# power.net
KiCad netlist of a schematic drawn in Altium Designer
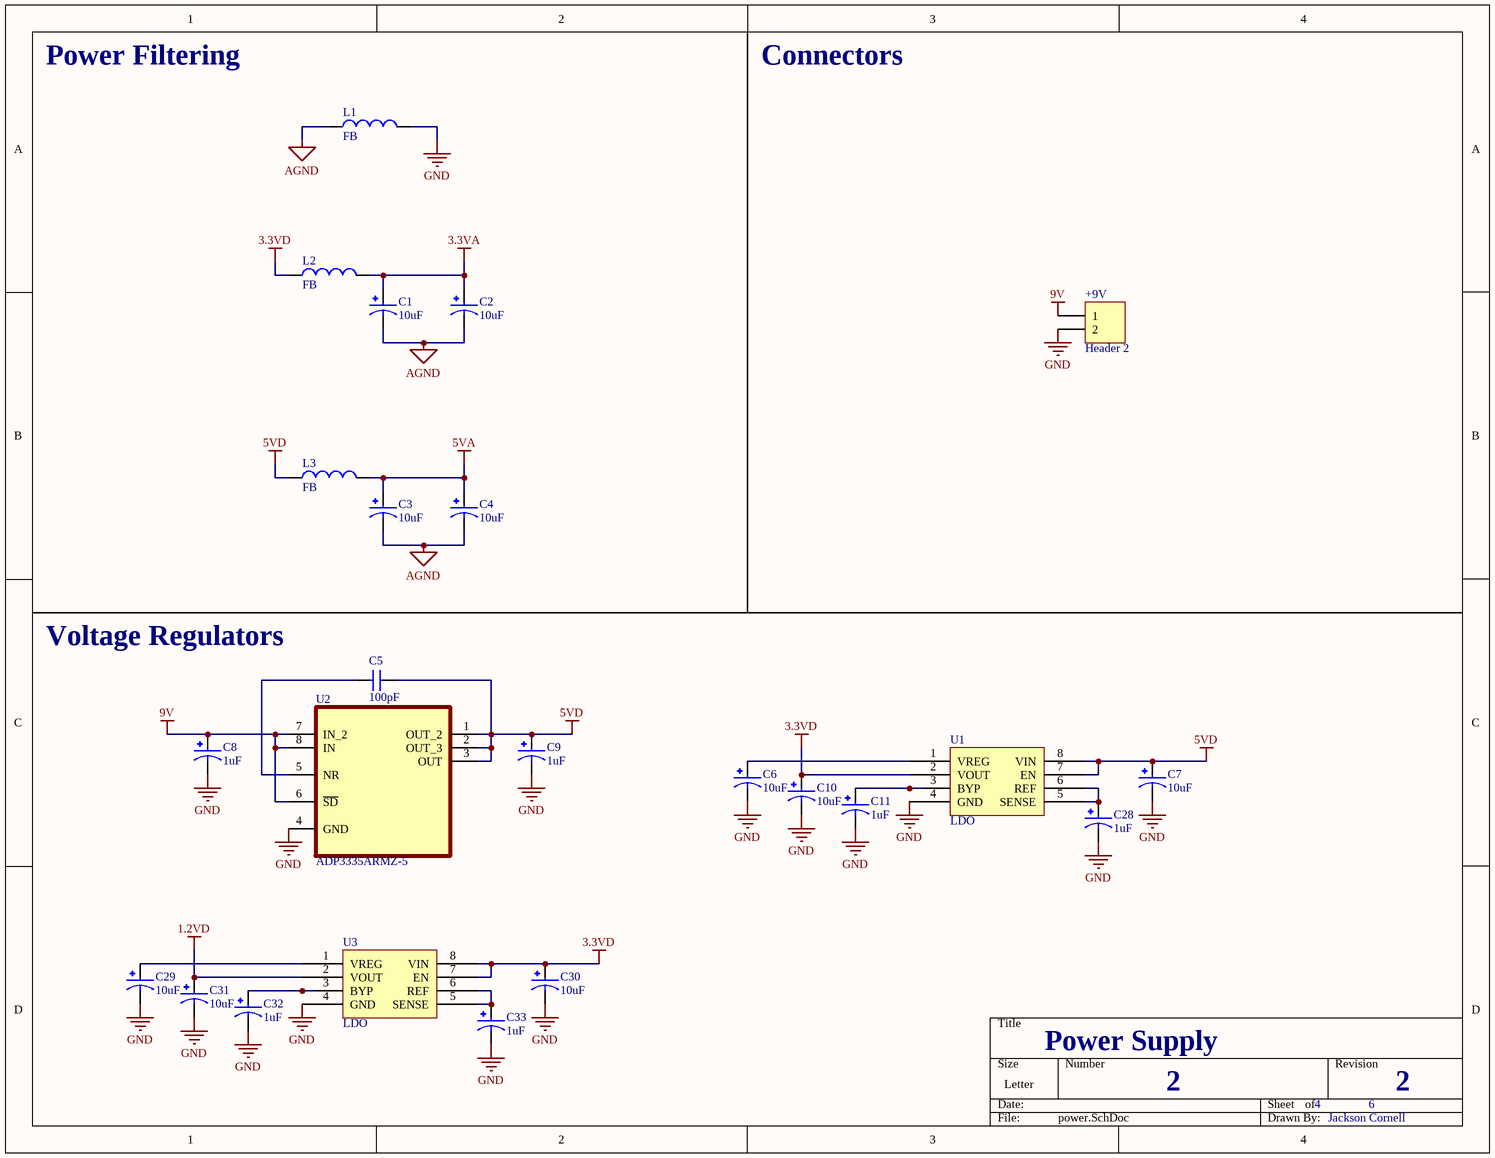
[diagram p0: power.SchDoc]

(export (version "E")
  (design (tool "Eeschema 10.0.6"))
  (components
    (comp (ref "+9V")
      (value "Header 2")
      (footprint "HDR1X2")
      (description "Header, 2-Pin")
      (fields (field (name "PUBLISHER") "Altium Limited"))
      (libsource (lib "Miscellaneous Connectors") (part "Header 2"))
    )
    (comp (ref "C1")
      (value "10uF")
      (footprint "CAPPRD200W50D500H1250")
      (description "Aluminum Electrolytic Capacitors, 220uF, 6.3V, -40 to 105C")
      (fields (field (name "MF") "Panasonic") (field (name "MP") "EEUFS0J221B"))
      (libsource (lib "EEUFS0J221B") (part "EEUFS0J221B"))
    )
    (comp (ref "C2")
      (value "10uF")
      (footprint "CAPPRD200W50D500H1250")
      (description "Aluminum Electrolytic Capacitors, 220uF, 6.3V, -40 to 105C")
      (fields (field (name "MF") "Panasonic") (field (name "MP") "EEUFS0J221B"))
      (libsource (lib "EEUFS0J221B") (part "EEUFS0J221B"))
    )
    (comp (ref "C3")
      (value "10uF")
      (footprint "CAPPRD200W50D500H1250")
      (description "Aluminum Electrolytic Capacitors, 220uF, 6.3V, -40 to 105C")
      (fields (field (name "MF") "Panasonic") (field (name "MP") "EEUFS0J221B"))
      (libsource (lib "EEUFS0J221B") (part "EEUFS0J221B"))
    )
    (comp (ref "C4")
      (value "10uF")
      (footprint "CAPPRD200W50D500H1250")
      (description "Aluminum Electrolytic Capacitors, 220uF, 6.3V, -40 to 105C")
      (fields (field (name "MF") "Panasonic") (field (name "MP") "EEUFS0J221B"))
      (libsource (lib "EEUFS0J221B") (part "EEUFS0J221B"))
    )
    (comp (ref "C5")
      (value "100pF")
      (footprint "CAPC0805")
      (fields (field (name "Comment") "Cap"))
      (libsource (lib "Passives") (part "Cap"))
    )
    (comp (ref "C6")
      (value "10uF")
      (footprint "CAPPRD200W50D500H1250")
      (description "Aluminum Electrolytic Capacitors, 220uF, 6.3V, -40 to 105C")
      (fields (field (name "MF") "Panasonic") (field (name "MP") "EEUFS0J221B"))
      (libsource (lib "EEUFS0J221B") (part "EEUFS0J221B"))
    )
    (comp (ref "C7")
      (value "10uF")
      (footprint "CAPPRD200W50D500H1250")
      (description "Aluminum Electrolytic Capacitors, 220uF, 6.3V, -40 to 105C")
      (fields (field (name "MF") "Panasonic") (field (name "MP") "EEUFS0J221B"))
      (libsource (lib "EEUFS0J221B") (part "EEUFS0J221B"))
    )
    (comp (ref "C8")
      (value "1uF")
      (footprint "CAPPRD200W50D500H1250")
      (description "Aluminum Electrolytic Capacitors, 220uF, 6.3V, -40 to 105C")
      (fields (field (name "MF") "Panasonic") (field (name "MP") "EEUFS0J221B"))
      (libsource (lib "EEUFS0J221B") (part "EEUFS0J221B"))
    )
    (comp (ref "C9")
      (value "1uF")
      (footprint "CAPPRD200W50D500H1250")
      (description "Aluminum Electrolytic Capacitors, 220uF, 6.3V, -40 to 105C")
      (fields (field (name "MF") "Panasonic") (field (name "MP") "EEUFS0J221B"))
      (libsource (lib "EEUFS0J221B") (part "EEUFS0J221B"))
    )
    (comp (ref "C10")
      (value "10uF")
      (footprint "CAPPRD200W50D500H1250")
      (description "Aluminum Electrolytic Capacitors, 220uF, 6.3V, -40 to 105C")
      (fields (field (name "MF") "Panasonic") (field (name "MP") "EEUFS0J221B"))
      (libsource (lib "EEUFS0J221B") (part "EEUFS0J221B"))
    )
    (comp (ref "C11")
      (value "1uF")
      (footprint "CAPPRD200W50D500H1250")
      (description "Aluminum Electrolytic Capacitors, 220uF, 6.3V, -40 to 105C")
      (fields (field (name "MF") "Panasonic") (field (name "MP") "EEUFS0J221B"))
      (libsource (lib "EEUFS0J221B") (part "EEUFS0J221B"))
    )
    (comp (ref "C28")
      (value "1uF")
      (footprint "CAPPRD200W50D500H1250")
      (description "Aluminum Electrolytic Capacitors, 220uF, 6.3V, -40 to 105C")
      (fields (field (name "MF") "Panasonic") (field (name "MP") "EEUFS0J221B"))
      (libsource (lib "EEUFS0J221B") (part "EEUFS0J221B"))
    )
    (comp (ref "C29")
      (value "10uF")
      (footprint "CAPPRD200W50D500H1250")
      (description "Aluminum Electrolytic Capacitors, 220uF, 6.3V, -40 to 105C")
      (fields (field (name "MF") "Panasonic") (field (name "MP") "EEUFS0J221B"))
      (libsource (lib "EEUFS0J221B") (part "EEUFS0J221B"))
    )
    (comp (ref "C30")
      (value "10uF")
      (footprint "CAPPRD200W50D500H1250")
      (description "Aluminum Electrolytic Capacitors, 220uF, 6.3V, -40 to 105C")
      (fields (field (name "MF") "Panasonic") (field (name "MP") "EEUFS0J221B"))
      (libsource (lib "EEUFS0J221B") (part "EEUFS0J221B"))
    )
    (comp (ref "C31")
      (value "10uF")
      (footprint "CAPPRD200W50D500H1250")
      (description "Aluminum Electrolytic Capacitors, 220uF, 6.3V, -40 to 105C")
      (fields (field (name "MF") "Panasonic") (field (name "MP") "EEUFS0J221B"))
      (libsource (lib "EEUFS0J221B") (part "EEUFS0J221B"))
    )
    (comp (ref "C32")
      (value "1uF")
      (footprint "CAPPRD200W50D500H1250")
      (description "Aluminum Electrolytic Capacitors, 220uF, 6.3V, -40 to 105C")
      (fields (field (name "MF") "Panasonic") (field (name "MP") "EEUFS0J221B"))
      (libsource (lib "EEUFS0J221B") (part "EEUFS0J221B"))
    )
    (comp (ref "C33")
      (value "1uF")
      (footprint "CAPPRD200W50D500H1250")
      (description "Aluminum Electrolytic Capacitors, 220uF, 6.3V, -40 to 105C")
      (fields (field (name "MF") "Panasonic") (field (name "MP") "EEUFS0J221B"))
      (libsource (lib "EEUFS0J221B") (part "EEUFS0J221B"))
    )
    (comp (ref "L1")
      (value "FB")
      (footprint "RES0805")
      (description "Inductor")
      (fields (field (name "PUBLISHER") "Altium Limited"))
      (libsource (lib "Miscellaneous Devices") (part "Inductor"))
    )
    (comp (ref "L2")
      (value "FB")
      (footprint "RES0805")
      (description "Inductor")
      (fields (field (name "PUBLISHER") "Altium Limited"))
      (libsource (lib "Miscellaneous Devices") (part "Inductor"))
    )
    (comp (ref "L3")
      (value "FB")
      (footprint "RES0805")
      (description "Inductor")
      (fields (field (name "PUBLISHER") "Altium Limited"))
      (libsource (lib "Miscellaneous Devices") (part "Inductor"))
    )
    (comp (ref "U1")
      (value "LDO")
      (footprint "SOIC127P600X175-9N")
      (libsource (lib "ADM7154") (part "ADM7154"))
    )
    (comp (ref "U2")
      (value "ADP3335ARMZ-5")
      (footprint "SOP65P490X110-8N")
      (description "Linear Voltage Regulator IC 1 Output 500mA 8-MSOP")
      (fields (field (name "MP") "ADP3335ARMZ-3.3") (field (name "MF") "Analog Devices"))
      (libsource (lib "ADP3335ARMZ-3.3") (part "ADP3335ARMZ-3.3"))
    )
    (comp (ref "U3")
      (value "LDO")
      (footprint "SOIC127P600X175-9N")
      (libsource (lib "ADM7154") (part "ADM7154"))
    )
  )
  (nets
    (net (code "1") (name "1.2VD") (class "Default")
      (node (ref "C31") (pin "P") (pinfunction "P_P") (pintype "passive"))
      (node (ref "U3") (pin "2") (pinfunction "VOUT_2") (pintype "passive"))
    )
    (net (code "2") (name "3.3VA") (class "Default")
      (node (ref "C1") (pin "P") (pinfunction "P_P") (pintype "passive"))
      (node (ref "C2") (pin "P") (pinfunction "P_P") (pintype "passive"))
      (node (ref "L2") (pin "2") (pinfunction "2_2") (pintype "passive"))
    )
    (net (code "3") (name "3.3VD") (class "Default")
      (node (ref "C10") (pin "P") (pinfunction "P_P") (pintype "passive"))
      (node (ref "C30") (pin "P") (pinfunction "P_P") (pintype "passive"))
      (node (ref "L2") (pin "1") (pinfunction "1_1") (pintype "passive"))
      (node (ref "U1") (pin "2") (pinfunction "VOUT_2") (pintype "passive"))
      (node (ref "U3") (pin "7") (pinfunction "EN_7") (pintype "passive"))
      (node (ref "U3") (pin "8") (pinfunction "VIN_8") (pintype "passive"))
    )
    (net (code "4") (name "5VA") (class "Default")
      (node (ref "C3") (pin "P") (pinfunction "P_P") (pintype "passive"))
      (node (ref "C4") (pin "P") (pinfunction "P_P") (pintype "passive"))
      (node (ref "L3") (pin "2") (pinfunction "2_2") (pintype "passive"))
    )
    (net (code "5") (name "5VD") (class "Default")
      (node (ref "C5") (pin "2") (pinfunction "B_2") (pintype "passive"))
      (node (ref "C7") (pin "P") (pinfunction "P_P") (pintype "passive"))
      (node (ref "C9") (pin "P") (pinfunction "P_P") (pintype "passive"))
      (node (ref "L3") (pin "1") (pinfunction "1_1") (pintype "passive"))
      (node (ref "U1") (pin "7") (pinfunction "EN_7") (pintype "passive"))
      (node (ref "U1") (pin "8") (pinfunction "VIN_8") (pintype "passive"))
      (node (ref "U2") (pin "1") (pinfunction "OUT_2_1") (pintype "passive"))
      (node (ref "U2") (pin "2") (pinfunction "OUT_3_2") (pintype "passive"))
      (node (ref "U2") (pin "3") (pinfunction "OUT_3") (pintype "passive"))
    )
    (net (code "6") (name "9V") (class "Default")
      (node (ref "+9V") (pin "1") (pinfunction "1_1") (pintype "passive"))
      (node (ref "C8") (pin "P") (pinfunction "P_P") (pintype "passive"))
      (node (ref "U2") (pin "6") (pinfunction "~{SD}_6") (pintype "passive"))
      (node (ref "U2") (pin "7") (pinfunction "IN_2_7") (pintype "passive"))
      (node (ref "U2") (pin "8") (pinfunction "IN_8") (pintype "passive"))
    )
    (net (code "7") (name "AGND") (class "Default")
      (node (ref "C1") (pin "N") (pinfunction "N_N") (pintype "passive"))
      (node (ref "C2") (pin "N") (pinfunction "N_N") (pintype "passive"))
      (node (ref "C3") (pin "N") (pinfunction "N_N") (pintype "passive"))
      (node (ref "C4") (pin "N") (pinfunction "N_N") (pintype "passive"))
      (node (ref "L1") (pin "1") (pinfunction "1_1") (pintype "passive"))
    )
    (net (code "8") (name "GND") (class "Default")
      (node (ref "+9V") (pin "2") (pinfunction "2_2") (pintype "passive"))
      (node (ref "C10") (pin "N") (pinfunction "N_N") (pintype "passive"))
      (node (ref "C11") (pin "N") (pinfunction "N_N") (pintype "passive"))
      (node (ref "C28") (pin "N") (pinfunction "N_N") (pintype "passive"))
      (node (ref "C29") (pin "N") (pinfunction "N_N") (pintype "passive"))
      (node (ref "C30") (pin "N") (pinfunction "N_N") (pintype "passive"))
      (node (ref "C31") (pin "N") (pinfunction "N_N") (pintype "passive"))
      (node (ref "C32") (pin "N") (pinfunction "N_N") (pintype "passive"))
      (node (ref "C33") (pin "N") (pinfunction "N_N") (pintype "passive"))
      (node (ref "C6") (pin "N") (pinfunction "N_N") (pintype "passive"))
      (node (ref "C7") (pin "N") (pinfunction "N_N") (pintype "passive"))
      (node (ref "C8") (pin "N") (pinfunction "N_N") (pintype "passive"))
      (node (ref "C9") (pin "N") (pinfunction "N_N") (pintype "passive"))
      (node (ref "L1") (pin "2") (pinfunction "2_2") (pintype "passive"))
      (node (ref "U1") (pin "4") (pinfunction "GND_4") (pintype "passive"))
      (node (ref "U2") (pin "4") (pinfunction "GND_4") (pintype "passive"))
      (node (ref "U3") (pin "4") (pinfunction "GND_4") (pintype "passive"))
    )
    (net (code "9") (name "Net-(C5-A)") (class "Default")
      (node (ref "C5") (pin "1") (pinfunction "A_1") (pintype "passive"))
      (node (ref "U2") (pin "5") (pinfunction "NR_5") (pintype "passive"))
    )
    (net (code "10") (name "Net-(U1-BYP)") (class "Default")
      (node (ref "C11") (pin "P") (pinfunction "P_P") (pintype "passive"))
      (node (ref "U1") (pin "3") (pinfunction "BYP_3") (pintype "passive"))
    )
    (net (code "11") (name "Net-(U1-REF)") (class "Default")
      (node (ref "C28") (pin "P") (pinfunction "P_P") (pintype "passive"))
      (node (ref "U1") (pin "5") (pinfunction "SENSE_5") (pintype "passive"))
      (node (ref "U1") (pin "6") (pinfunction "REF_6") (pintype "passive"))
    )
    (net (code "12") (name "Net-(U1-VREG)") (class "Default")
      (node (ref "C6") (pin "P") (pinfunction "P_P") (pintype "passive"))
      (node (ref "U1") (pin "1") (pinfunction "VREG_1") (pintype "passive"))
    )
    (net (code "13") (name "Net-(U3-BYP)") (class "Default")
      (node (ref "C32") (pin "P") (pinfunction "P_P") (pintype "passive"))
      (node (ref "U3") (pin "3") (pinfunction "BYP_3") (pintype "passive"))
    )
    (net (code "14") (name "Net-(U3-REF)") (class "Default")
      (node (ref "C33") (pin "P") (pinfunction "P_P") (pintype "passive"))
      (node (ref "U3") (pin "5") (pinfunction "SENSE_5") (pintype "passive"))
      (node (ref "U3") (pin "6") (pinfunction "REF_6") (pintype "passive"))
    )
    (net (code "15") (name "Net-(U3-VREG)") (class "Default")
      (node (ref "C29") (pin "P") (pinfunction "P_P") (pintype "passive"))
      (node (ref "U3") (pin "1") (pinfunction "VREG_1") (pintype "passive"))
    )
  )
)
